# Main.net
KiCad netlist of a schematic drawn in Altium Designer
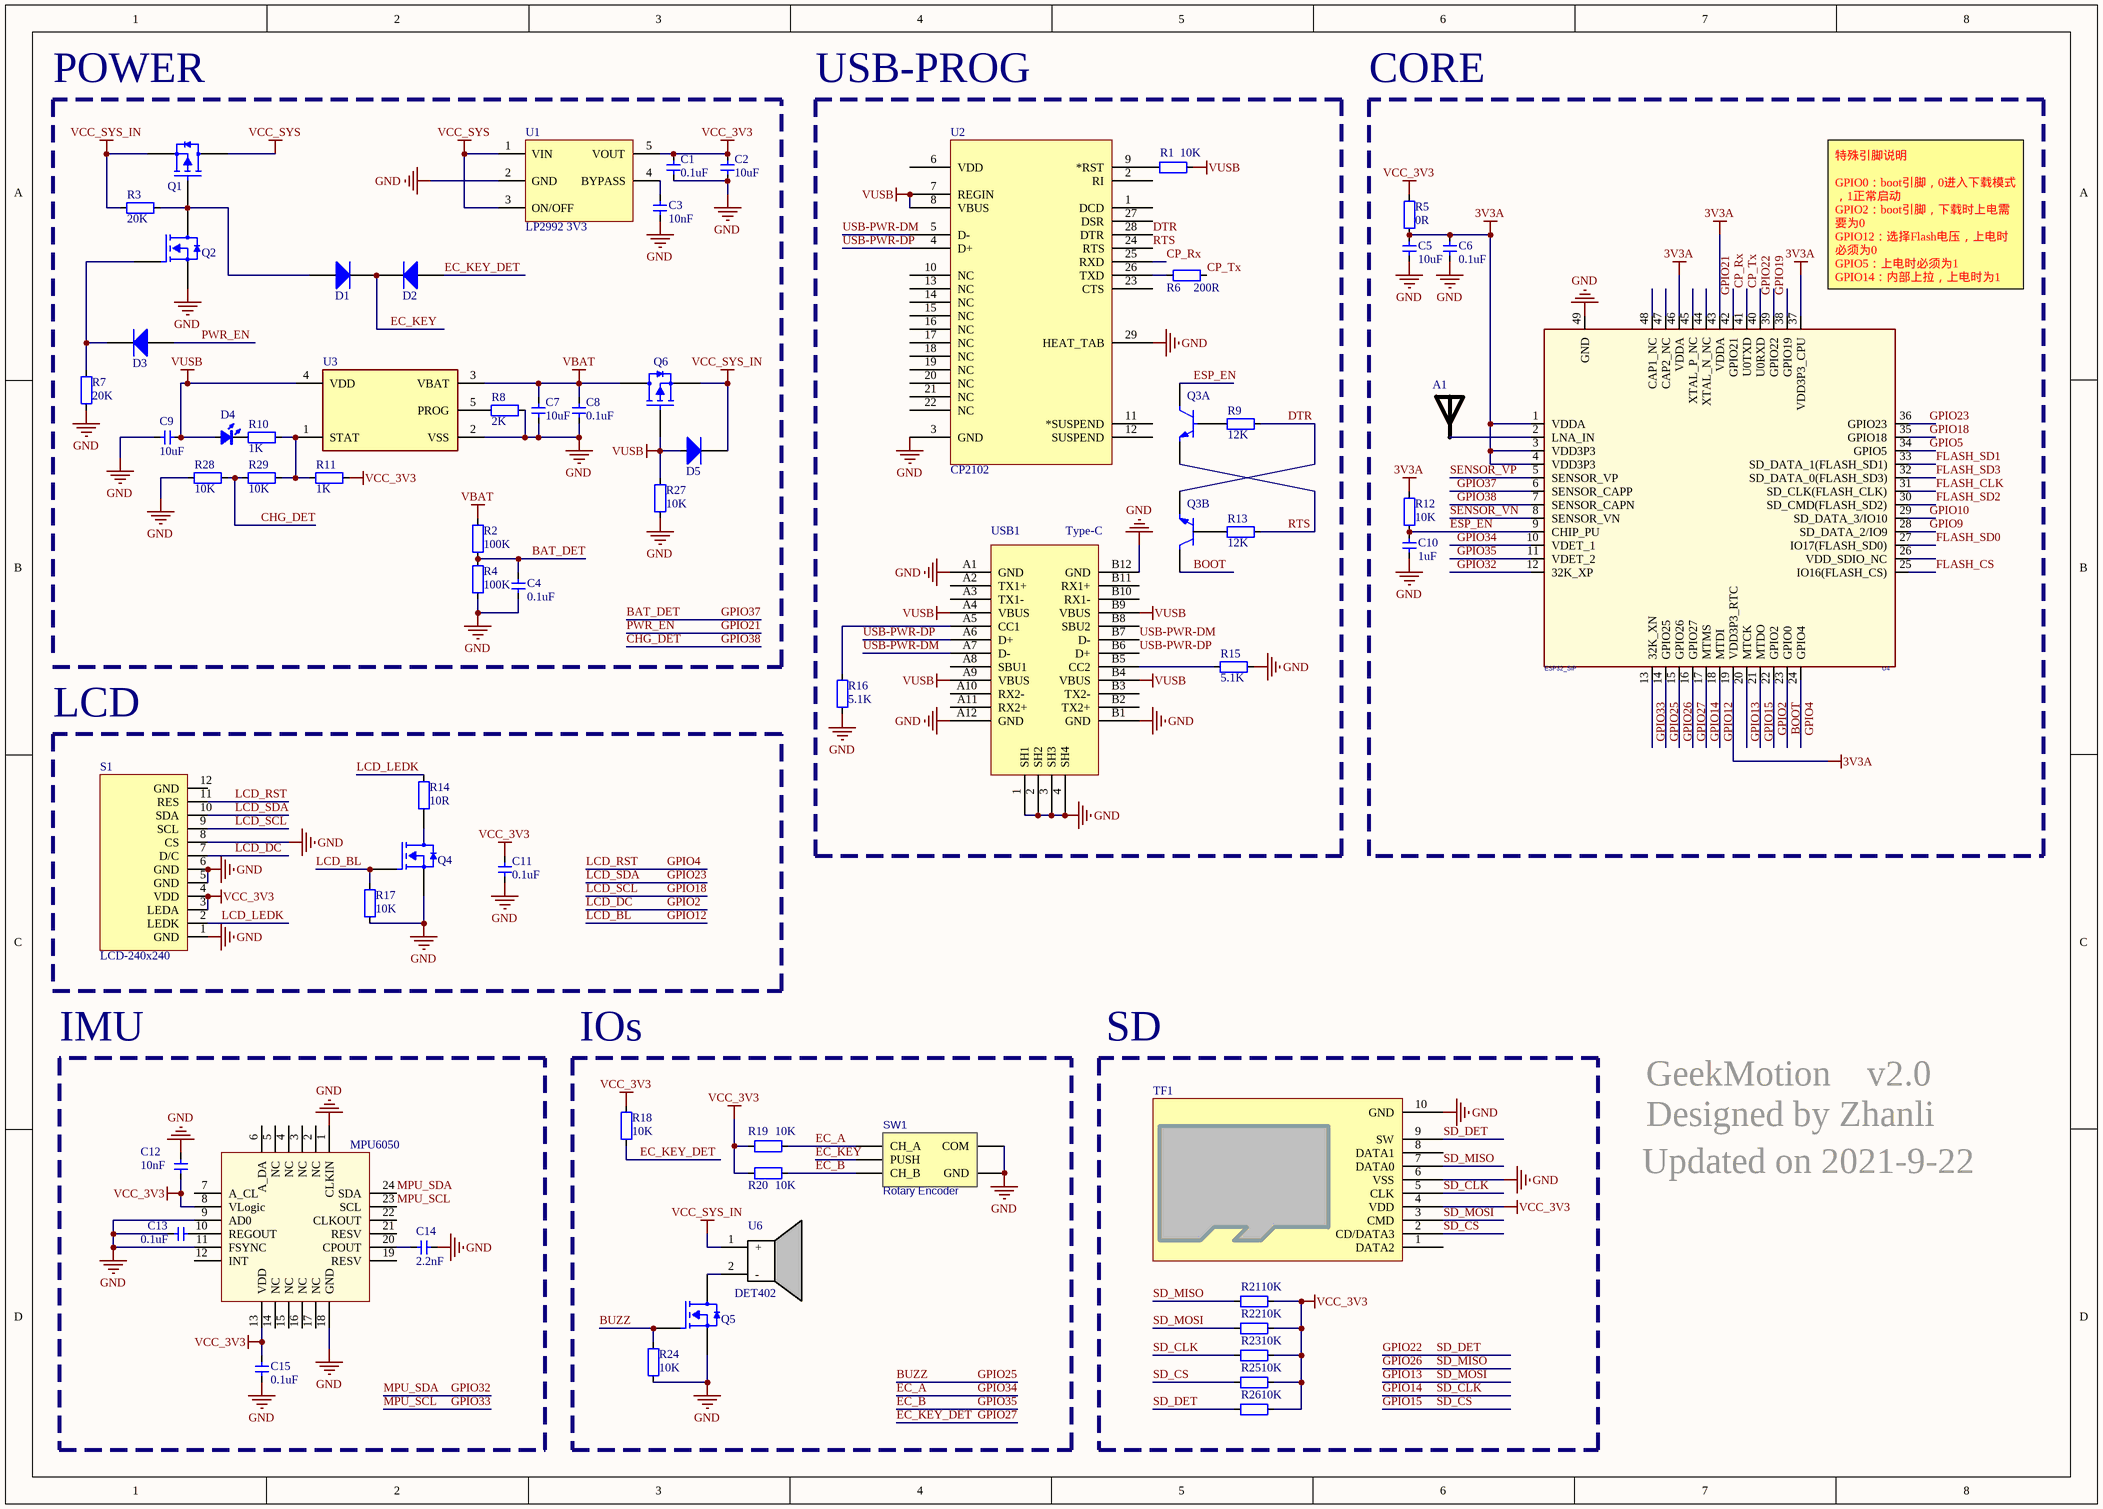
[diagram p0: Main.SchDoc]

(export (version "E")
  (design (tool "Eeschema 10.0.6"))
  (components
    (comp (ref "A1")
      (value "RAINSUN")
      (footprint "ANT-Rainsun-AN5120")
      (libsource (lib "MyPcbLib") (part "ANT-Rainsun-AP5120"))
    )
    (comp (ref "C1")
      (value "0.1uF")
      (footprint "CAP_0402")
      (description "Capacitor")
      (libsource (lib "MyPcbLib") (part "电容-0402"))
    )
    (comp (ref "C2")
      (value "10uF")
      (footprint "CAP_0402")
      (description "Capacitor")
      (libsource (lib "MyPcbLib") (part "电容-0402"))
    )
    (comp (ref "C3")
      (value "10nF")
      (footprint "CAP_0402")
      (description "Capacitor")
      (libsource (lib "MyPcbLib") (part "电容-0402"))
    )
    (comp (ref "C4")
      (value "0.1uF")
      (footprint "CAP_0402")
      (description "Capacitor")
      (libsource (lib "MyPcbLib") (part "电容-0402"))
    )
    (comp (ref "C5")
      (value "10uF")
      (footprint "CAP_0402")
      (description "Capacitor")
      (libsource (lib "MyPcbLib") (part "电容-0402"))
    )
    (comp (ref "C6")
      (value "0.1uF")
      (footprint "CAP_0402")
      (description "Capacitor")
      (libsource (lib "MyPcbLib") (part "电容-0402"))
    )
    (comp (ref "C7")
      (value "10uF")
      (footprint "CAP_0402")
      (description "Capacitor")
      (libsource (lib "MyPcbLib") (part "电容-0402"))
    )
    (comp (ref "C8")
      (value "0.1uF")
      (footprint "CAP_0402")
      (description "Capacitor")
      (libsource (lib "MyPcbLib") (part "电容-0402"))
    )
    (comp (ref "C9")
      (value "10uF")
      (footprint "CAP_0402")
      (description "Capacitor")
      (libsource (lib "MyPcbLib") (part "电容-0402"))
    )
    (comp (ref "C10")
      (value "1uF")
      (footprint "CAP_0402")
      (description "Capacitor")
      (libsource (lib "MyPcbLib") (part "电容-0402"))
    )
    (comp (ref "C11")
      (value "0.1uF")
      (footprint "CAP_0402")
      (description "Capacitor")
      (libsource (lib "MyPcbLib") (part "电容-0402"))
    )
    (comp (ref "C12")
      (value "10nF")
      (footprint "CAP_0402")
      (description "Capacitor")
      (libsource (lib "MyPcbLib") (part "电容-0402"))
    )
    (comp (ref "C13")
      (value "0.1uF")
      (footprint "CAP_0402")
      (description "Capacitor")
      (libsource (lib "MyPcbLib") (part "电容-0402"))
    )
    (comp (ref "C14")
      (value "2.2nF")
      (footprint "CAP_0402")
      (description "Capacitor")
      (libsource (lib "MyPcbLib") (part "电容-0402"))
    )
    (comp (ref "C15")
      (value "0.1uF")
      (footprint "CAP_0402")
      (description "Capacitor")
      (libsource (lib "MyPcbLib") (part "电容-0402"))
    )
    (comp (ref "D1")
      (value "二极管-5819W")
      (footprint "SOD-323")
      (description "40V")
      (libsource (lib "MyPcbLib") (part "二极管-5819W"))
    )
    (comp (ref "D2")
      (value "二极管-5819W")
      (footprint "SOD-323")
      (description "40V")
      (libsource (lib "MyPcbLib") (part "二极管-5819W"))
    )
    (comp (ref "D3")
      (value "二极管-5819W")
      (footprint "SOD-323")
      (description "40V")
      (libsource (lib "MyPcbLib") (part "二极管-5819W"))
    )
    (comp (ref "D4")
      (value "color?")
      (footprint "LED_0402_RED")
      (description "LED")
      (libsource (lib "KitSprout") (part "LED_0402"))
    )
    (comp (ref "D5")
      (value "二极管-5819W")
      (footprint "SOD-323")
      (description "40V")
      (libsource (lib "Peak") (part "二极管-5819W"))
    )
    (comp (ref "Q1")
      (value "AO3401A")
      (footprint "SOT23-3")
      (description "P-MOS")
      (libsource (lib "MyPcbLib") (part "AO3401A"))
    )
    (comp (ref "Q2")
      (value "AO3400A")
      (footprint "SOT23-3")
      (description "N-MOS")
      (libsource (lib "MyPcbLib") (part "AO3400A"))
    )
    (comp (ref "Q3")
      (value "BC847BVC-7")
      (footprint "SOT563-6")
      (libsource (lib "MyPcbLib") (part "BC847BVC-7"))
    )
    (comp (ref "Q4")
      (value "AO3400A")
      (footprint "SOT23-3")
      (description "N-MOS")
      (libsource (lib "MyPcbLib") (part "AO3400A"))
    )
    (comp (ref "Q5")
      (value "AO3400A")
      (footprint "SOT23-3")
      (description "N-MOS")
      (libsource (lib "MyPcbLib") (part "AO3400A"))
    )
    (comp (ref "Q6")
      (value "AO3401A")
      (footprint "SOT23-3")
      (description "P-MOS")
      (libsource (lib "MyPcbLib") (part "AO3401A"))
    )
    (comp (ref "R1")
      (value "10K")
      (footprint "RES_0402")
      (description "Resistor")
      (libsource (lib "MyPcbLib") (part "电阻-0402"))
    )
    (comp (ref "R2")
      (value "100K")
      (footprint "RES_0402")
      (description "Resistor")
      (libsource (lib "") (part "电阻-0402_2"))
    )
    (comp (ref "R3")
      (value "20K")
      (footprint "RES_0402")
      (description "Resistor")
      (libsource (lib "") (part "电阻-0402_3"))
    )
    (comp (ref "R4")
      (value "100K")
      (footprint "RES_0402")
      (description "Resistor")
      (libsource (lib "") (part "电阻-0402_2"))
    )
    (comp (ref "R5")
      (value "0R")
      (footprint "RES_0402")
      (description "Resistor")
      (libsource (lib "") (part "电阻-0402_1"))
    )
    (comp (ref "R6")
      (value "200R")
      (footprint "RES_0402")
      (description "Resistor")
      (libsource (lib "MyPcbLib") (part "电阻-0402"))
    )
    (comp (ref "R7")
      (value "20K")
      (footprint "RES_0402")
      (description "Resistor")
      (libsource (lib "") (part "电阻-0402_2"))
    )
    (comp (ref "R8")
      (value "2K")
      (footprint "RES_0402")
      (description "Resistor")
      (libsource (lib "") (part "电阻-0402_3"))
    )
    (comp (ref "R9")
      (value "12K")
      (footprint "RES_0402")
      (description "Resistor")
      (libsource (lib "MyPcbLib") (part "电阻-0402"))
    )
    (comp (ref "R10")
      (value "1K")
      (footprint "RES_0402")
      (description "Resistor")
      (libsource (lib "") (part "电阻-0402_3"))
    )
    (comp (ref "R11")
      (value "1K")
      (footprint "RES_0402")
      (description "Resistor")
      (libsource (lib "") (part "电阻-0402_3"))
    )
    (comp (ref "R12")
      (value "10K")
      (footprint "RES_0402")
      (description "Resistor")
      (libsource (lib "") (part "电阻-0402_1"))
    )
    (comp (ref "R13")
      (value "12K")
      (footprint "RES_0402")
      (description "Resistor")
      (libsource (lib "MyPcbLib") (part "电阻-0402"))
    )
    (comp (ref "R14")
      (value "10R")
      (footprint "RES_0402")
      (description "Resistor")
      (libsource (lib "") (part "电阻-0402_2"))
    )
    (comp (ref "R15")
      (value "5.1K")
      (footprint "RES_0402")
      (description "Resistor")
      (libsource (lib "MyPcbLib") (part "电阻-0402"))
    )
    (comp (ref "R16")
      (value "5.1K")
      (footprint "RES_0402")
      (description "Resistor")
      (libsource (lib "") (part "电阻-0402_1"))
    )
    (comp (ref "R17")
      (value "10K")
      (footprint "RES_0402")
      (description "Resistor")
      (libsource (lib "") (part "电阻-0402_2"))
    )
    (comp (ref "R18")
      (value "10K")
      (footprint "RES_0402")
      (description "Resistor")
      (libsource (lib "") (part "电阻-0402_1"))
    )
    (comp (ref "R19")
      (value "10K")
      (footprint "RES_0402")
      (description "Resistor")
      (libsource (lib "MyPcbLib") (part "电阻-0402"))
    )
    (comp (ref "R20")
      (value "10K")
      (footprint "RES_0402")
      (description "Resistor")
      (libsource (lib "MyPcbLib") (part "电阻-0402"))
    )
    (comp (ref "R21")
      (value "10K")
      (footprint "RES_0402")
      (description "Resistor")
      (libsource (lib "MyPcbLib") (part "电阻-0402"))
    )
    (comp (ref "R22")
      (value "10K")
      (footprint "RES_0402")
      (description "Resistor")
      (libsource (lib "MyPcbLib") (part "电阻-0402"))
    )
    (comp (ref "R23")
      (value "10K")
      (footprint "RES_0402")
      (description "Resistor")
      (libsource (lib "MyPcbLib") (part "电阻-0402"))
    )
    (comp (ref "R24")
      (value "10K")
      (footprint "RES_0402")
      (description "Resistor")
      (libsource (lib "") (part "电阻-0402_2"))
    )
    (comp (ref "R25")
      (value "10K")
      (footprint "RES_0402")
      (description "Resistor")
      (libsource (lib "MyPcbLib") (part "电阻-0402"))
    )
    (comp (ref "R26")
      (value "10K")
      (footprint "RES_0402")
      (description "Resistor")
      (libsource (lib "MyPcbLib") (part "电阻-0402"))
    )
    (comp (ref "R27")
      (value "10K")
      (footprint "RES_0402")
      (description "Resistor")
      (libsource (lib "") (part "电阻-0402_2"))
    )
    (comp (ref "R28")
      (value "10K")
      (footprint "Peak:RES_0402")
      (description "Resistor")
      (libsource (lib "MyPcbLib") (part "电阻-0402"))
    )
    (comp (ref "R29")
      (value "10K")
      (footprint "RES_0402")
      (description "Resistor")
      (libsource (lib "MyPcbLib") (part "电阻-0402"))
    )
    (comp (ref "S1")
      (value "LCD-240x240")
      (footprint "LCD-240x240-FlUSH-154")
      (description "显示屏")
      (libsource (lib "mLib") (part "LCD-240x240"))
    )
    (comp (ref "SW1")
      (value "Rotary Encoder")
      (footprint "SIQ-02FVS3")
      (fields
        (field (name "BOM_SUPPLIER PART") "C1322543")
        (field (name "BOM_MANUFACTURER PART") "EC11E1534443")
        (field (name "CONTRIBUTOR") "LCSC")
      )
      (libsource (lib "MyPcbLib") (part "Rotary Encoder"))
    )
    (comp (ref "TF1")
      (value "TF")
      (footprint "TF-SOCKET")
      (description "8脚自弹")
      (libsource (lib "MyPcbLib") (part "TF卡座"))
    )
    (comp (ref "U1")
      (value "LP2992 3V3")
      (footprint "SOT23-5")
      (description "LDO")
      (libsource (lib "mLib") (part "LP2992"))
    )
    (comp (ref "U2")
      (value "CP2102")
      (footprint "QFN-28")
      (description "USB转TTL")
      (libsource (lib "mLib") (part "CP2102"))
    )
    (comp (ref "U3")
      (value "MCP73831T")
      (footprint "SOT23-5")
      (libsource (lib "MyPcbLib") (part "MCP73831T"))
    )
    (comp (ref "U4")
      (value "ESP32_SIP")
      (footprint "QFN-48_7X7")
      (libsource (lib "mLib") (part "ESP32-PICO"))
    )
    (comp (ref "U5")
      (value "MPU6050")
      (footprint "QFN-24")
      (description "六轴传感器")
      (libsource (lib "mLib") (part "MPU6050"))
    )
    (comp (ref "U6") (value "DET402") (footprint "DET402") (libsource (lib "MyPcbLib") (part "DET402")))
    (comp (ref "USB1")
      (value "Type-C")
      (footprint "Type-C-TOP")
      (libsource (lib "MyPcbLib") (part "USB-Type-C-TOP"))
    )
  )
  (nets
    (net (code "1") (name "/BAT_DET") (class "Default")
      (node (ref "C4") (pin "2") (pinfunction "2_2") (pintype "passive"))
      (node (ref "R2") (pin "1") (pinfunction "1_1") (pintype "passive"))
      (node (ref "R4") (pin "2") (pinfunction "2_2") (pintype "passive"))
      (node (ref "U4") (pin "6") (pinfunction "SENSOR_CAPP_6") (pintype "passive"))
    )
    (net (code "2") (name "/BOOT") (class "Default")
      (node (ref "Q3") (pin "3") (pinfunction "C2_3") (pintype "passive"))
      (node (ref "U4") (pin "23") (pinfunction "GPIO0_23") (pintype "passive"))
    )
    (net (code "3") (name "/BUZZ") (class "Default")
      (node (ref "Q5") (pin "1") (pinfunction "G_1") (pintype "passive"))
      (node (ref "R24") (pin "2") (pinfunction "2_2") (pintype "passive"))
      (node (ref "U4") (pin "14") (pinfunction "GPIO25_14") (pintype "passive"))
    )
    (net (code "4") (name "/CHG_DET") (class "Default")
      (node (ref "R28") (pin "1") (pinfunction "1_1") (pintype "passive"))
      (node (ref "R29") (pin "2") (pinfunction "2_2") (pintype "passive"))
      (node (ref "U4") (pin "7") (pinfunction "SENSOR_CAPN_7") (pintype "passive"))
    )
    (net (code "5") (name "/CP_Rx") (class "Default")
      (node (ref "U2") (pin "25") (pinfunction "RXD_25") (pintype "passive"))
      (node (ref "U4") (pin "41") (pinfunction "U0TXD_41") (pintype "power_in"))
    )
    (net (code "6") (name "/CP_Tx") (class "Default")
      (node (ref "R6") (pin "1") (pinfunction "1_1") (pintype "passive"))
      (node (ref "U4") (pin "40") (pinfunction "U0RXD_40") (pintype "power_in"))
    )
    (net (code "7") (name "/DTR") (class "Default")
      (node (ref "Q3") (pin "4") (pinfunction "E2_4") (pintype "passive"))
      (node (ref "R9") (pin "1") (pinfunction "1_1") (pintype "passive"))
      (node (ref "U2") (pin "28") (pinfunction "DTR_28") (pintype "passive"))
    )
    (net (code "8") (name "/EC_A") (class "Default")
      (node (ref "R19") (pin "1") (pinfunction "1_1") (pintype "passive"))
      (node (ref "SW1") (pin "1") (pinfunction "CH_A_1") (pintype "passive"))
      (node (ref "U4") (pin "10") (pinfunction "VDET_1_10") (pintype "passive"))
    )
    (net (code "9") (name "/EC_B") (class "Default")
      (node (ref "R20") (pin "1") (pinfunction "1_1") (pintype "passive"))
      (node (ref "SW1") (pin "4") (pinfunction "CH_B_4") (pintype "passive"))
      (node (ref "U4") (pin "11") (pinfunction "VDET_2_11") (pintype "passive"))
    )
    (net (code "10") (name "/EC_KEY") (class "Default")
      (node (ref "D1") (pin "2") (pinfunction "K_2") (pintype "passive"))
      (node (ref "D2") (pin "2") (pinfunction "K_2") (pintype "passive"))
      (node (ref "SW1") (pin "2") (pinfunction "PUSH_2") (pintype "passive"))
    )
    (net (code "11") (name "/EC_KEY_DET") (class "Default")
      (node (ref "D2") (pin "1") (pinfunction "A_1") (pintype "passive"))
      (node (ref "R18") (pin "2") (pinfunction "2_2") (pintype "passive"))
      (node (ref "U4") (pin "16") (pinfunction "GPIO27_16") (pintype "passive"))
    )
    (net (code "12") (name "/ESP_EN") (class "Default")
      (node (ref "C10") (pin "1") (pinfunction "1_1") (pintype "passive"))
      (node (ref "Q3") (pin "6") (pinfunction "C1_6") (pintype "passive"))
      (node (ref "R12") (pin "2") (pinfunction "2_2") (pintype "passive"))
      (node (ref "U4") (pin "9") (pinfunction "CHIP_PU_9") (pintype "passive"))
    )
    (net (code "13") (name "/FLASH_CLK") (class "Default")
      (node (ref "U4") (pin "31") (pinfunction "SD_CLK(FLASH_CLK)_31") (pintype "passive"))
    )
    (net (code "14") (name "/FLASH_CS") (class "Default")
      (node (ref "U4") (pin "25") (pinfunction "IO16(FLASH_CS)_25") (pintype "passive"))
    )
    (net (code "15") (name "/FLASH_SD0") (class "Default")
      (node (ref "U4") (pin "27") (pinfunction "IO17(FLASH_SD0)_27") (pintype "passive"))
    )
    (net (code "16") (name "/FLASH_SD1") (class "Default")
      (node (ref "U4") (pin "33") (pinfunction "SD_DATA_1(FLASH_SD1)_33") (pintype "passive"))
    )
    (net (code "17") (name "/FLASH_SD2") (class "Default")
      (node (ref "U4") (pin "30") (pinfunction "SD_CMD(FLASH_SD2)_30") (pintype "passive"))
    )
    (net (code "18") (name "/FLASH_SD3") (class "Default")
      (node (ref "U4") (pin "32") (pinfunction "SD_DATA_0(FLASH_SD3)_32") (pintype "passive"))
    )
    (net (code "19") (name "/GPIO2") (class "Default")
      (node (ref "S1") (pin "7") (pinfunction "D/C_7") (pintype "passive"))
      (node (ref "U4") (pin "22") (pinfunction "GPIO2_22") (pintype "passive"))
    )
    (net (code "20") (name "/GPIO4") (class "Default")
      (node (ref "S1") (pin "11") (pinfunction "RES_11") (pintype "passive"))
      (node (ref "U4") (pin "24") (pinfunction "GPIO4_24") (pintype "passive"))
    )
    (net (code "21") (name "/GPIO5") (class "Default")
      (node (ref "U4") (pin "34") (pinfunction "GPIO5_34") (pintype "passive"))
    )
    (net (code "22") (name "/GPIO9") (class "Default")
      (node (ref "U4") (pin "28") (pinfunction "SD_DATA_2/IO9_28") (pintype "passive"))
    )
    (net (code "23") (name "/GPIO10") (class "Default")
      (node (ref "U4") (pin "29") (pinfunction "SD_DATA_3/IO10_29") (pintype "passive"))
    )
    (net (code "24") (name "/GPIO12") (class "Default")
      (node (ref "Q4") (pin "1") (pinfunction "G_1") (pintype "passive"))
      (node (ref "R17") (pin "2") (pinfunction "2_2") (pintype "passive"))
      (node (ref "U4") (pin "18") (pinfunction "MTDI_18") (pintype "passive"))
    )
    (net (code "25") (name "/GPIO13") (class "Default")
      (node (ref "R22") (pin "2") (pinfunction "2_2") (pintype "passive"))
      (node (ref "TF1") (pin "3") (pinfunction "CMD_3") (pintype "passive"))
      (node (ref "U4") (pin "20") (pinfunction "MTCK_20") (pintype "passive"))
    )
    (net (code "26") (name "/GPIO14") (class "Default")
      (node (ref "R23") (pin "2") (pinfunction "2_2") (pintype "passive"))
      (node (ref "TF1") (pin "5") (pinfunction "CLK_5") (pintype "passive"))
      (node (ref "U4") (pin "17") (pinfunction "MTMS_17") (pintype "passive"))
    )
    (net (code "27") (name "/GPIO15") (class "Default")
      (node (ref "R25") (pin "2") (pinfunction "2_2") (pintype "passive"))
      (node (ref "TF1") (pin "2") (pinfunction "CD/DATA3_2") (pintype "passive"))
      (node (ref "U4") (pin "21") (pinfunction "MTDO_21") (pintype "passive"))
    )
    (net (code "28") (name "/GPIO18") (class "Default")
      (node (ref "S1") (pin "9") (pinfunction "SCL_9") (pintype "passive"))
      (node (ref "U4") (pin "35") (pinfunction "GPIO18_35") (pintype "passive"))
    )
    (net (code "29") (name "/GPIO19") (class "Default")
      (node (ref "U4") (pin "38") (pinfunction "GPIO19_38") (pintype "passive"))
    )
    (net (code "30") (name "/GPIO21") (class "Default")
      (node (ref "D3") (pin "1") (pinfunction "A_1") (pintype "passive"))
      (node (ref "U4") (pin "42") (pinfunction "GPIO21_42") (pintype "passive"))
    )
    (net (code "31") (name "/GPIO22") (class "Default")
      (node (ref "R26") (pin "2") (pinfunction "2_2") (pintype "passive"))
      (node (ref "TF1") (pin "9") (pinfunction "SW_9") (pintype "passive"))
      (node (ref "U4") (pin "39") (pinfunction "GPIO22_39") (pintype "passive"))
    )
    (net (code "32") (name "/GPIO23") (class "Default")
      (node (ref "S1") (pin "10") (pinfunction "SDA_10") (pintype "passive"))
      (node (ref "U4") (pin "36") (pinfunction "GPIO23_36") (pintype "passive"))
    )
    (net (code "33") (name "/GPIO26") (class "Default")
      (node (ref "R21") (pin "2") (pinfunction "2_2") (pintype "passive"))
      (node (ref "TF1") (pin "7") (pinfunction "DATA0_7") (pintype "passive"))
      (node (ref "U4") (pin "15") (pinfunction "GPIO26_15") (pintype "passive"))
    )
    (net (code "34") (name "/GPIO32") (class "Default")
      (node (ref "U4") (pin "12") (pinfunction "32K_XP_12") (pintype "passive"))
      (node (ref "U5") (pin "24") (pinfunction "SDA_24") (pintype "passive"))
    )
    (net (code "35") (name "/GPIO33") (class "Default")
      (node (ref "U4") (pin "13") (pinfunction "32K_XN_13") (pintype "passive"))
      (node (ref "U5") (pin "23") (pinfunction "SCL_23") (pintype "passive"))
    )
    (net (code "36") (name "/LCD_LEDK") (class "Default")
      (node (ref "R14") (pin "2") (pinfunction "2_2") (pintype "passive"))
      (node (ref "S1") (pin "2") (pinfunction "LEDK_2") (pintype "passive"))
    )
    (net (code "37") (name "/RTS") (class "Default")
      (node (ref "Q3") (pin "1") (pinfunction "E1_1") (pintype "passive"))
      (node (ref "R13") (pin "1") (pinfunction "1_1") (pintype "passive"))
      (node (ref "U2") (pin "24") (pinfunction "RTS_24") (pintype "passive"))
    )
    (net (code "38") (name "/SENSOR_VN") (class "Default")
      (node (ref "U4") (pin "8") (pinfunction "SENSOR_VN_8") (pintype "passive"))
    )
    (net (code "39") (name "/SENSOR_VP") (class "Default")
      (node (ref "U4") (pin "5") (pinfunction "SENSOR_VP_5") (pintype "passive"))
    )
    (net (code "40") (name "/USB-PWR-DM") (class "Default")
      (node (ref "U2") (pin "5") (pinfunction "D-_5") (pintype "passive"))
      (node (ref "USB1") (pin "A7") (pinfunction "D-_A7") (pintype "passive"))
      (node (ref "USB1") (pin "B7") (pinfunction "D-_B7") (pintype "passive"))
    )
    (net (code "41") (name "/USB-PWR-DP") (class "Default")
      (node (ref "U2") (pin "4") (pinfunction "D+_4") (pintype "passive"))
      (node (ref "USB1") (pin "A6") (pinfunction "D+_A6") (pintype "passive"))
      (node (ref "USB1") (pin "B6") (pinfunction "D+_B6") (pintype "passive"))
    )
    (net (code "42") (name "3V3A") (class "Default")
      (node (ref "C5") (pin "2") (pinfunction "2_2") (pintype "passive"))
      (node (ref "C6") (pin "2") (pinfunction "2_2") (pintype "passive"))
      (node (ref "R12") (pin "1") (pinfunction "1_1") (pintype "passive"))
      (node (ref "R5") (pin "2") (pinfunction "2_2") (pintype "passive"))
      (node (ref "U4") (pin "1") (pinfunction "VDDA_1") (pintype "power_in"))
      (node (ref "U4") (pin "19") (pinfunction "VDD3P3_RTC_19") (pintype "power_in"))
      (node (ref "U4") (pin "3") (pinfunction "VDD3P3_3") (pintype "power_in"))
      (node (ref "U4") (pin "37") (pinfunction "VDD3P3_CPU_37") (pintype "power_in"))
      (node (ref "U4") (pin "4") (pinfunction "VDD3P3_4") (pintype "power_in"))
      (node (ref "U4") (pin "43") (pinfunction "VDDA_43") (pintype "power_in"))
      (node (ref "U4") (pin "46") (pinfunction "VDDA_46") (pintype "power_in"))
    )
    (net (code "43") (name "GND") (class "Default")
      (node (ref "C1") (pin "1") (pinfunction "1_1") (pintype "passive"))
      (node (ref "C10") (pin "2") (pinfunction "2_2") (pintype "passive"))
      (node (ref "C11") (pin "1") (pinfunction "1_1") (pintype "passive"))
      (node (ref "C12") (pin "2") (pinfunction "2_2") (pintype "passive"))
      (node (ref "C13") (pin "2") (pinfunction "2_2") (pintype "passive"))
      (node (ref "C14") (pin "1") (pinfunction "1_1") (pintype "passive"))
      (node (ref "C15") (pin "1") (pinfunction "1_1") (pintype "passive"))
      (node (ref "C2") (pin "1") (pinfunction "1_1") (pintype "passive"))
      (node (ref "C3") (pin "1") (pinfunction "1_1") (pintype "passive"))
      (node (ref "C4") (pin "1") (pinfunction "1_1") (pintype "passive"))
      (node (ref "C5") (pin "1") (pinfunction "1_1") (pintype "passive"))
      (node (ref "C6") (pin "1") (pinfunction "1_1") (pintype "passive"))
      (node (ref "C7") (pin "1") (pinfunction "1_1") (pintype "passive"))
      (node (ref "C8") (pin "1") (pinfunction "1_1") (pintype "passive"))
      (node (ref "C9") (pin "1") (pinfunction "1_1") (pintype "passive"))
      (node (ref "Q2") (pin "2") (pinfunction "S_2") (pintype "passive"))
      (node (ref "Q4") (pin "2") (pinfunction "S_2") (pintype "passive"))
      (node (ref "Q5") (pin "2") (pinfunction "S_2") (pintype "passive"))
      (node (ref "R15") (pin "1") (pinfunction "1_1") (pintype "passive"))
      (node (ref "R16") (pin "2") (pinfunction "2_2") (pintype "passive"))
      (node (ref "R17") (pin "1") (pinfunction "1_1") (pintype "passive"))
      (node (ref "R24") (pin "1") (pinfunction "1_1") (pintype "passive"))
      (node (ref "R27") (pin "1") (pinfunction "1_1") (pintype "passive"))
      (node (ref "R28") (pin "2") (pinfunction "2_2") (pintype "passive"))
      (node (ref "R4") (pin "1") (pinfunction "1_1") (pintype "passive"))
      (node (ref "R7") (pin "1") (pinfunction "1_1") (pintype "passive"))
      (node (ref "R8") (pin "2") (pinfunction "2_2") (pintype "passive"))
      (node (ref "S1") (pin "1") (pinfunction "GND_1") (pintype "passive"))
      (node (ref "S1") (pin "5") (pinfunction "GND_5") (pintype "passive"))
      (node (ref "S1") (pin "6") (pinfunction "GND_6") (pintype "passive"))
      (node (ref "S1") (pin "8") (pinfunction "CS_8") (pintype "passive"))
      (node (ref "SW1") (pin "3") (pinfunction "COM_3") (pintype "passive"))
      (node (ref "SW1") (pin "5") (pinfunction "GND_5") (pintype "passive"))
      (node (ref "TF1") (pin "10") (pinfunction "GND_10") (pintype "passive"))
      (node (ref "TF1") (pin "6") (pinfunction "VSS_6") (pintype "passive"))
      (node (ref "U1") (pin "2") (pinfunction "GND_2") (pintype "passive"))
      (node (ref "U2") (pin "29") (pinfunction "HEAT_TAB_29") (pintype "passive"))
      (node (ref "U2") (pin "3") (pinfunction "GND_3") (pintype "passive"))
      (node (ref "U3") (pin "2") (pinfunction "VSS_2") (pintype "power_in"))
      (node (ref "U4") (pin "49") (pinfunction "GND_49") (pintype "power_in"))
      (node (ref "U5") (pin "1") (pinfunction "CLKIN_1") (pintype "passive"))
      (node (ref "U5") (pin "11") (pinfunction "FSYNC_11") (pintype "passive"))
      (node (ref "U5") (pin "18") (pinfunction "GND_18") (pintype "passive"))
      (node (ref "U5") (pin "9") (pinfunction "AD0_9") (pintype "passive"))
      (node (ref "USB1") (pin "1") (pinfunction "SH1_1") (pintype "passive"))
      (node (ref "USB1") (pin "2") (pinfunction "SH2_2") (pintype "passive"))
      (node (ref "USB1") (pin "3") (pinfunction "SH3_3") (pintype "passive"))
      (node (ref "USB1") (pin "4") (pinfunction "SH4_4") (pintype "passive"))
      (node (ref "USB1") (pin "A1") (pinfunction "GND_A1") (pintype "passive"))
      (node (ref "USB1") (pin "A12") (pinfunction "GND_A12") (pintype "passive"))
      (node (ref "USB1") (pin "B1") (pinfunction "GND_B1") (pintype "passive"))
      (node (ref "USB1") (pin "B12") (pinfunction "GND_B12") (pintype "passive"))
    )
    (net (code "44") (name "Net-(D1-A)") (class "Default")
      (node (ref "D1") (pin "1") (pinfunction "A_1") (pintype "passive"))
      (node (ref "Q1") (pin "1") (pinfunction "G_1") (pintype "passive"))
      (node (ref "Q2") (pin "3") (pinfunction "D_3") (pintype "passive"))
      (node (ref "R3") (pin "2") (pinfunction "2_2") (pintype "passive"))
    )
    (net (code "45") (name "Net-(D3-K)") (class "Default")
      (node (ref "D3") (pin "2") (pinfunction "K_2") (pintype "passive"))
      (node (ref "Q2") (pin "1") (pinfunction "G_1") (pintype "passive"))
      (node (ref "R7") (pin "2") (pinfunction "2_2") (pintype "passive"))
    )
    (net (code "46") (name "Net-(D4-K)") (class "Default")
      (node (ref "D4") (pin "2") (pinfunction "K_2") (pintype "passive"))
      (node (ref "R10") (pin "1") (pinfunction "1_1") (pintype "passive"))
    )
    (net (code "47") (name "Net-(Q3A-B1)") (class "Default")
      (node (ref "Q3") (pin "2") (pinfunction "B1_2") (pintype "passive"))
      (node (ref "R9") (pin "2") (pinfunction "2_2") (pintype "passive"))
    )
    (net (code "48") (name "Net-(Q3B-B2)") (class "Default")
      (node (ref "Q3") (pin "5") (pinfunction "B2_5") (pintype "passive"))
      (node (ref "R13") (pin "2") (pinfunction "2_2") (pintype "passive"))
    )
    (net (code "49") (name "Net-(Q4-D)") (class "Default")
      (node (ref "Q4") (pin "3") (pinfunction "D_3") (pintype "passive"))
      (node (ref "R14") (pin "1") (pinfunction "1_1") (pintype "passive"))
    )
    (net (code "50") (name "Net-(Q5-D)") (class "Default")
      (node (ref "Q5") (pin "3") (pinfunction "D_3") (pintype "passive"))
      (node (ref "U6") (pin "2") (pinfunction "-_2") (pintype "passive"))
    )
    (net (code "51") (name "Net-(U1-BYPASS)") (class "Default")
      (node (ref "C3") (pin "2") (pinfunction "2_2") (pintype "passive"))
      (node (ref "U1") (pin "4") (pinfunction "BYPASS_4") (pintype "passive"))
    )
    (net (code "52") (name "Net-(U2-*RST)") (class "Default")
      (node (ref "R1") (pin "2") (pinfunction "2_2") (pintype "passive"))
      (node (ref "U2") (pin "9") (pinfunction "*RST_9") (pintype "passive"))
    )
    (net (code "53") (name "Net-(U2-TXD)") (class "Default")
      (node (ref "R6") (pin "2") (pinfunction "2_2") (pintype "passive"))
      (node (ref "U2") (pin "26") (pinfunction "TXD_26") (pintype "passive"))
    )
    (net (code "54") (name "Net-(U3-PROG)") (class "Default")
      (node (ref "R8") (pin "1") (pinfunction "1_1") (pintype "passive"))
      (node (ref "U3") (pin "5") (pinfunction "PROG_5") (pintype "passive"))
    )
    (net (code "55") (name "Net-(U3-STAT)") (class "Default")
      (node (ref "R10") (pin "2") (pinfunction "2_2") (pintype "passive"))
      (node (ref "R11") (pin "1") (pinfunction "1_1") (pintype "passive"))
      (node (ref "R29") (pin "1") (pinfunction "1_1") (pintype "passive"))
      (node (ref "U3") (pin "1") (pinfunction "STAT_1") (pintype "passive"))
    )
    (net (code "56") (name "Net-(U4-LNA_IN)") (class "Default")
      (node (ref "A1") (pin "1") (pinfunction "1_1") (pintype "passive"))
      (node (ref "U4") (pin "2") (pinfunction "LNA_IN_2") (pintype "passive"))
    )
    (net (code "57") (name "Net-(U5-CPOUT)") (class "Default")
      (node (ref "C14") (pin "2") (pinfunction "2_2") (pintype "passive"))
      (node (ref "U5") (pin "20") (pinfunction "CPOUT_20") (pintype "passive"))
    )
    (net (code "58") (name "Net-(U5-REGOUT)") (class "Default")
      (node (ref "C13") (pin "1") (pinfunction "1_1") (pintype "passive"))
      (node (ref "U5") (pin "10") (pinfunction "REGOUT_10") (pintype "passive"))
    )
    (net (code "59") (name "Net-(USB1-CC1)") (class "Default")
      (node (ref "R16") (pin "1") (pinfunction "1_1") (pintype "passive"))
      (node (ref "USB1") (pin "A5") (pinfunction "CC1_A5") (pintype "passive"))
    )
    (net (code "60") (name "Net-(USB1-CC2)") (class "Default")
      (node (ref "R15") (pin "2") (pinfunction "2_2") (pintype "passive"))
      (node (ref "USB1") (pin "B5") (pinfunction "CC2_B5") (pintype "passive"))
    )
    (net (code "61") (name "VBAT") (class "Default")
      (node (ref "C7") (pin "2") (pinfunction "2_2") (pintype "passive"))
      (node (ref "C8") (pin "2") (pinfunction "2_2") (pintype "passive"))
      (node (ref "Q6") (pin "3") (pinfunction "D_3") (pintype "passive"))
      (node (ref "R2") (pin "2") (pinfunction "2_2") (pintype "passive"))
      (node (ref "U3") (pin "3") (pinfunction "VBAT_3") (pintype "power_in"))
    )
    (net (code "62") (name "VCC_3V3") (class "Default")
      (node (ref "C1") (pin "2") (pinfunction "2_2") (pintype "passive"))
      (node (ref "C11") (pin "2") (pinfunction "2_2") (pintype "passive"))
      (node (ref "C12") (pin "1") (pinfunction "1_1") (pintype "passive"))
      (node (ref "C15") (pin "2") (pinfunction "2_2") (pintype "passive"))
      (node (ref "C2") (pin "2") (pinfunction "2_2") (pintype "passive"))
      (node (ref "R11") (pin "2") (pinfunction "2_2") (pintype "passive"))
      (node (ref "R18") (pin "1") (pinfunction "1_1") (pintype "passive"))
      (node (ref "R19") (pin "2") (pinfunction "2_2") (pintype "passive"))
      (node (ref "R20") (pin "2") (pinfunction "2_2") (pintype "passive"))
      (node (ref "R21") (pin "1") (pinfunction "1_1") (pintype "passive"))
      (node (ref "R22") (pin "1") (pinfunction "1_1") (pintype "passive"))
      (node (ref "R23") (pin "1") (pinfunction "1_1") (pintype "passive"))
      (node (ref "R25") (pin "1") (pinfunction "1_1") (pintype "passive"))
      (node (ref "R26") (pin "1") (pinfunction "1_1") (pintype "passive"))
      (node (ref "R5") (pin "1") (pinfunction "1_1") (pintype "passive"))
      (node (ref "S1") (pin "3") (pinfunction "LEDA_3") (pintype "passive"))
      (node (ref "S1") (pin "4") (pinfunction "VDD_4") (pintype "passive"))
      (node (ref "TF1") (pin "4") (pinfunction "VDD_4") (pintype "passive"))
      (node (ref "U1") (pin "5") (pinfunction "VOUT_5") (pintype "passive"))
      (node (ref "U5") (pin "13") (pinfunction "VDD_13") (pintype "passive"))
      (node (ref "U5") (pin "8") (pinfunction "VLogic_8") (pintype "passive"))
    )
    (net (code "63") (name "VCC_SYS") (class "Default")
      (node (ref "Q1") (pin "3") (pinfunction "D_3") (pintype "passive"))
      (node (ref "U1") (pin "1") (pinfunction "VIN_1") (pintype "passive"))
      (node (ref "U1") (pin "3") (pinfunction "ON/OFF_3") (pintype "passive"))
    )
    (net (code "64") (name "VCC_SYS_IN") (class "Default")
      (node (ref "D5") (pin "2") (pinfunction "K_2") (pintype "passive"))
      (node (ref "Q1") (pin "2") (pinfunction "S_2") (pintype "passive"))
      (node (ref "Q6") (pin "2") (pinfunction "S_2") (pintype "passive"))
      (node (ref "R3") (pin "1") (pinfunction "1_1") (pintype "passive"))
      (node (ref "U6") (pin "1") (pinfunction "+_1") (pintype "passive"))
    )
    (net (code "65") (name "VUSB") (class "Default")
      (node (ref "C9") (pin "2") (pinfunction "2_2") (pintype "passive"))
      (node (ref "D4") (pin "1") (pinfunction "A_1") (pintype "passive"))
      (node (ref "D5") (pin "1") (pinfunction "A_1") (pintype "passive"))
      (node (ref "Q6") (pin "1") (pinfunction "G_1") (pintype "passive"))
      (node (ref "R1") (pin "1") (pinfunction "1_1") (pintype "passive"))
      (node (ref "R27") (pin "2") (pinfunction "2_2") (pintype "passive"))
      (node (ref "U2") (pin "7") (pinfunction "REGIN_7") (pintype "passive"))
      (node (ref "U2") (pin "8") (pinfunction "VBUS_8") (pintype "passive"))
      (node (ref "U3") (pin "4") (pinfunction "VDD_4") (pintype "power_in"))
      (node (ref "USB1") (pin "A4") (pinfunction "VBUS_A4") (pintype "passive"))
      (node (ref "USB1") (pin "A9") (pinfunction "VBUS_A9") (pintype "passive"))
      (node (ref "USB1") (pin "B4") (pinfunction "VBUS_B4") (pintype "passive"))
      (node (ref "USB1") (pin "B9") (pinfunction "VBUS_B9") (pintype "passive"))
    )
    (net (code "66") (name "unconnected-(S1-GND-Pad12)") (class "Default")
      (node (ref "S1") (pin "12") (pinfunction "GND_12") (pintype "passive"))
    )
    (net (code "67") (name "unconnected-(TF1-DATA1-Pad8)") (class "Default")
      (node (ref "TF1") (pin "8") (pinfunction "DATA1_8") (pintype "passive"))
    )
    (net (code "68") (name "unconnected-(TF1-DATA2-Pad1)") (class "Default")
      (node (ref "TF1") (pin "1") (pinfunction "DATA2_1") (pintype "passive"))
    )
    (net (code "69") (name "unconnected-(U2-*SUSPEND-Pad11)") (class "Default")
      (node (ref "U2") (pin "11") (pinfunction "*SUSPEND_11") (pintype "passive"))
    )
    (net (code "70") (name "unconnected-(U2-CTS-Pad23)") (class "Default")
      (node (ref "U2") (pin "23") (pinfunction "CTS_23") (pintype "passive"))
    )
    (net (code "71") (name "unconnected-(U2-DCD-Pad1)") (class "Default")
      (node (ref "U2") (pin "1") (pinfunction "DCD_1") (pintype "passive"))
    )
    (net (code "72") (name "unconnected-(U2-DSR-Pad27)") (class "Default")
      (node (ref "U2") (pin "27") (pinfunction "DSR_27") (pintype "passive"))
    )
    (net (code "73") (name "unconnected-(U2-NC-Pad10)") (class "Default")
      (node (ref "U2") (pin "10") (pinfunction "NC_10") (pintype "passive"))
    )
    (net (code "74") (name "unconnected-(U2-NC-Pad13)") (class "Default")
      (node (ref "U2") (pin "13") (pinfunction "NC_13") (pintype "passive"))
    )
    (net (code "75") (name "unconnected-(U2-NC-Pad14)") (class "Default")
      (node (ref "U2") (pin "14") (pinfunction "NC_14") (pintype "passive"))
    )
    (net (code "76") (name "unconnected-(U2-NC-Pad15)") (class "Default")
      (node (ref "U2") (pin "15") (pinfunction "NC_15") (pintype "passive"))
    )
    (net (code "77") (name "unconnected-(U2-NC-Pad16)") (class "Default")
      (node (ref "U2") (pin "16") (pinfunction "NC_16") (pintype "passive"))
    )
    (net (code "78") (name "unconnected-(U2-NC-Pad17)") (class "Default")
      (node (ref "U2") (pin "17") (pinfunction "NC_17") (pintype "passive"))
    )
    (net (code "79") (name "unconnected-(U2-NC-Pad18)") (class "Default")
      (node (ref "U2") (pin "18") (pinfunction "NC_18") (pintype "passive"))
    )
    (net (code "80") (name "unconnected-(U2-NC-Pad19)") (class "Default")
      (node (ref "U2") (pin "19") (pinfunction "NC_19") (pintype "passive"))
    )
    (net (code "81") (name "unconnected-(U2-NC-Pad20)") (class "Default")
      (node (ref "U2") (pin "20") (pinfunction "NC_20") (pintype "passive"))
    )
    (net (code "82") (name "unconnected-(U2-NC-Pad21)") (class "Default")
      (node (ref "U2") (pin "21") (pinfunction "NC_21") (pintype "passive"))
    )
    (net (code "83") (name "unconnected-(U2-NC-Pad22)") (class "Default")
      (node (ref "U2") (pin "22") (pinfunction "NC_22") (pintype "passive"))
    )
    (net (code "84") (name "unconnected-(U2-RI-Pad2)") (class "Default")
      (node (ref "U2") (pin "2") (pinfunction "RI_2") (pintype "passive"))
    )
    (net (code "85") (name "unconnected-(U2-SUSPEND-Pad12)") (class "Default")
      (node (ref "U2") (pin "12") (pinfunction "SUSPEND_12") (pintype "passive"))
    )
    (net (code "86") (name "unconnected-(U2-VDD-Pad6)") (class "Default")
      (node (ref "U2") (pin "6") (pinfunction "VDD_6") (pintype "passive"))
    )
    (net (code "87") (name "unconnected-(U4-CAP1_NC-Pad48)") (class "Default")
      (node (ref "U4") (pin "48") (pinfunction "CAP1_NC_48") (pintype "passive"))
    )
    (net (code "88") (name "unconnected-(U4-CAP2_NC-Pad47)") (class "Default")
      (node (ref "U4") (pin "47") (pinfunction "CAP2_NC_47") (pintype "passive"))
    )
    (net (code "89") (name "unconnected-(U4-VDD_SDIO_NC-Pad26)") (class "Default")
      (node (ref "U4") (pin "26") (pinfunction "VDD_SDIO_NC_26") (pintype "passive"))
    )
    (net (code "90") (name "unconnected-(U4-XTAL_N_NC-Pad44)") (class "Default")
      (node (ref "U4") (pin "44") (pinfunction "XTAL_N_NC_44") (pintype "passive"))
    )
    (net (code "91") (name "unconnected-(U4-XTAL_P_NC-Pad45)") (class "Default")
      (node (ref "U4") (pin "45") (pinfunction "XTAL_P_NC_45") (pintype "passive"))
    )
    (net (code "92") (name "unconnected-(U5-A_CL-Pad7)") (class "Default")
      (node (ref "U5") (pin "7") (pinfunction "A_CL_7") (pintype "passive"))
    )
    (net (code "93") (name "unconnected-(U5-A_DA-Pad6)") (class "Default")
      (node (ref "U5") (pin "6") (pinfunction "A_DA_6") (pintype "passive"))
    )
    (net (code "94") (name "unconnected-(U5-CLKOUT-Pad22)") (class "Default")
      (node (ref "U5") (pin "22") (pinfunction "CLKOUT_22") (pintype "passive"))
    )
    (net (code "95") (name "unconnected-(U5-INT-Pad12)") (class "Default")
      (node (ref "U5") (pin "12") (pinfunction "INT_12") (pintype "passive"))
    )
    (net (code "96") (name "unconnected-(U5-NC-Pad2)") (class "Default")
      (node (ref "U5") (pin "2") (pinfunction "NC_2") (pintype "passive"))
    )
    (net (code "97") (name "unconnected-(U5-NC-Pad3)") (class "Default")
      (node (ref "U5") (pin "3") (pinfunction "NC_3") (pintype "passive"))
    )
    (net (code "98") (name "unconnected-(U5-NC-Pad4)") (class "Default")
      (node (ref "U5") (pin "4") (pinfunction "NC_4") (pintype "passive"))
    )
    (net (code "99") (name "unconnected-(U5-NC-Pad5)") (class "Default")
      (node (ref "U5") (pin "5") (pinfunction "NC_5") (pintype "passive"))
    )
    (net (code "100") (name "unconnected-(U5-NC-Pad14)") (class "Default")
      (node (ref "U5") (pin "14") (pinfunction "NC_14") (pintype "passive"))
    )
    (net (code "101") (name "unconnected-(U5-NC-Pad15)") (class "Default")
      (node (ref "U5") (pin "15") (pinfunction "NC_15") (pintype "passive"))
    )
    (net (code "102") (name "unconnected-(U5-NC-Pad16)") (class "Default")
      (node (ref "U5") (pin "16") (pinfunction "NC_16") (pintype "passive"))
    )
    (net (code "103") (name "unconnected-(U5-NC-Pad17)") (class "Default")
      (node (ref "U5") (pin "17") (pinfunction "NC_17") (pintype "passive"))
    )
    (net (code "104") (name "unconnected-(U5-RESV-Pad19)") (class "Default")
      (node (ref "U5") (pin "19") (pinfunction "RESV_19") (pintype "passive"))
    )
    (net (code "105") (name "unconnected-(U5-RESV-Pad21)") (class "Default")
      (node (ref "U5") (pin "21") (pinfunction "RESV_21") (pintype "passive"))
    )
    (net (code "106") (name "unconnected-(USB1-RX1+-PadB11)") (class "Default")
      (node (ref "USB1") (pin "B11") (pinfunction "RX1+_B11") (pintype "passive"))
    )
    (net (code "107") (name "unconnected-(USB1-RX1--PadB10)") (class "Default")
      (node (ref "USB1") (pin "B10") (pinfunction "RX1-_B10") (pintype "passive"))
    )
    (net (code "108") (name "unconnected-(USB1-RX2+-PadA11)") (class "Default")
      (node (ref "USB1") (pin "A11") (pinfunction "RX2+_A11") (pintype "passive"))
    )
    (net (code "109") (name "unconnected-(USB1-RX2--PadA10)") (class "Default")
      (node (ref "USB1") (pin "A10") (pinfunction "RX2-_A10") (pintype "passive"))
    )
    (net (code "110") (name "unconnected-(USB1-SBU1-PadA8)") (class "Default")
      (node (ref "USB1") (pin "A8") (pinfunction "SBU1_A8") (pintype "passive"))
    )
    (net (code "111") (name "unconnected-(USB1-SBU2-PadB8)") (class "Default")
      (node (ref "USB1") (pin "B8") (pinfunction "SBU2_B8") (pintype "passive"))
    )
    (net (code "112") (name "unconnected-(USB1-TX1+-PadA2)") (class "Default")
      (node (ref "USB1") (pin "A2") (pinfunction "TX1+_A2") (pintype "passive"))
    )
    (net (code "113") (name "unconnected-(USB1-TX1--PadA3)") (class "Default")
      (node (ref "USB1") (pin "A3") (pinfunction "TX1-_A3") (pintype "passive"))
    )
    (net (code "114") (name "unconnected-(USB1-TX2+-PadB2)") (class "Default")
      (node (ref "USB1") (pin "B2") (pinfunction "TX2+_B2") (pintype "passive"))
    )
    (net (code "115") (name "unconnected-(USB1-TX2--PadB3)") (class "Default")
      (node (ref "USB1") (pin "B3") (pinfunction "TX2-_B3") (pintype "passive"))
    )
  )
)
